# IRComms.net
KiCad netlist of a schematic drawn in Altium Designer
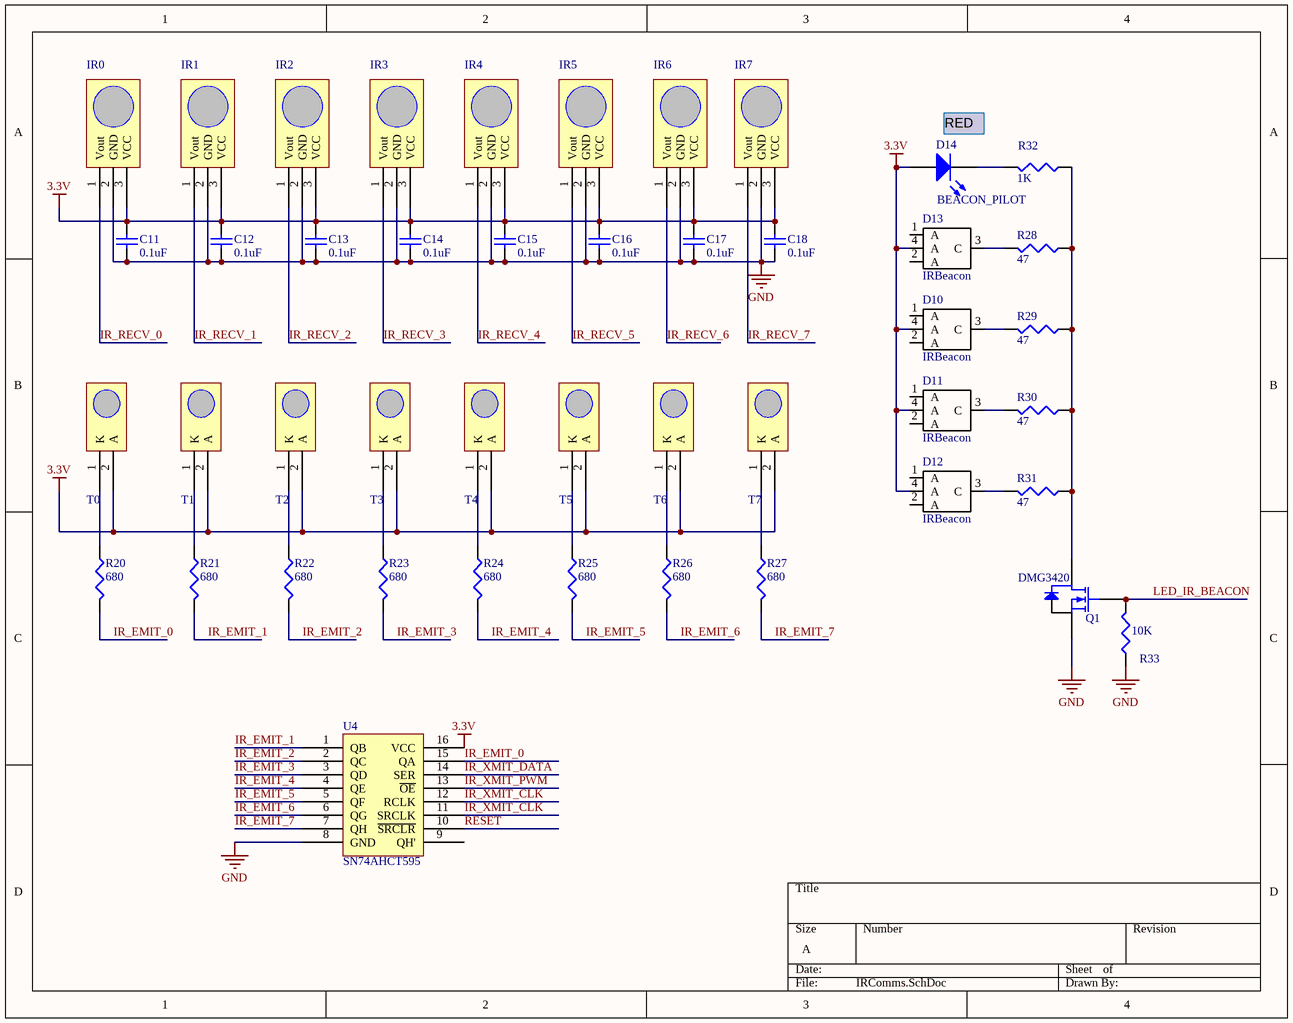
[diagram p0: IRComms.SchDoc]

(export (version "E")
  (design (tool "Eeschema 10.0.6"))
  (components
    (comp (ref "C11")
      (value "0.1uF")
      (footprint "CAPC1005L")
      (description "Capacitor (Semiconductor SIM Model)")
      (fields (field (name "Comment") "Cap Semi") (field (name "PUBLISHER") "Altium Limited"))
      (libsource (lib "Miscellaneous Devices") (part "Cap Semi"))
    )
    (comp (ref "C12")
      (value "0.1uF")
      (footprint "CAPC1005L")
      (description "Capacitor (Semiconductor SIM Model)")
      (fields (field (name "Comment") "Cap Semi") (field (name "PUBLISHER") "Altium Limited"))
      (libsource (lib "Miscellaneous Devices") (part "Cap Semi"))
    )
    (comp (ref "C13")
      (value "0.1uF")
      (footprint "CAPC1005L")
      (description "Capacitor (Semiconductor SIM Model)")
      (fields (field (name "Comment") "Cap Semi") (field (name "PUBLISHER") "Altium Limited"))
      (libsource (lib "Miscellaneous Devices") (part "Cap Semi"))
    )
    (comp (ref "C14")
      (value "0.1uF")
      (footprint "CAPC1005L")
      (description "Capacitor (Semiconductor SIM Model)")
      (fields (field (name "Comment") "Cap Semi") (field (name "PUBLISHER") "Altium Limited"))
      (libsource (lib "Miscellaneous Devices") (part "Cap Semi"))
    )
    (comp (ref "C15")
      (value "0.1uF")
      (footprint "CAPC1005L")
      (description "Capacitor (Semiconductor SIM Model)")
      (fields (field (name "Comment") "Cap Semi") (field (name "PUBLISHER") "Altium Limited"))
      (libsource (lib "Miscellaneous Devices") (part "Cap Semi"))
    )
    (comp (ref "C16")
      (value "0.1uF")
      (footprint "CAPC1005L")
      (description "Capacitor (Semiconductor SIM Model)")
      (fields (field (name "Comment") "Cap Semi") (field (name "PUBLISHER") "Altium Limited"))
      (libsource (lib "Miscellaneous Devices") (part "Cap Semi"))
    )
    (comp (ref "C17")
      (value "0.1uF")
      (footprint "CAPC1005L")
      (description "Capacitor (Semiconductor SIM Model)")
      (fields (field (name "Comment") "Cap Semi") (field (name "PUBLISHER") "Altium Limited"))
      (libsource (lib "Miscellaneous Devices") (part "Cap Semi"))
    )
    (comp (ref "C18")
      (value "0.1uF")
      (footprint "CAPC1005L")
      (description "Capacitor (Semiconductor SIM Model)")
      (fields (field (name "Comment") "Cap Semi") (field (name "PUBLISHER") "Altium Limited"))
      (libsource (lib "Miscellaneous Devices") (part "Cap Semi"))
    )
    (comp (ref "D10") (value "IRBeacon") (footprint "IRBeacon") (libsource (lib "mrone") (part "IRBeacon")))
    (comp (ref "D11") (value "IRBeacon") (footprint "IRBeacon") (libsource (lib "mrone") (part "IRBeacon")))
    (comp (ref "D12") (value "IRBeacon") (footprint "IRBeacon") (libsource (lib "mrone") (part "IRBeacon")))
    (comp (ref "D13") (value "IRBeacon") (footprint "IRBeacon") (libsource (lib "mrone") (part "IRBeacon")))
    (comp (ref "D14")
      (value "BEACON_PILOT")
      (footprint "SurfaceMount(603)")
      (libsource (lib "mrone") (part "LED"))
    )
    (comp (ref "IR0")
      (value "GP1UX31QS")
      (footprint "GP1UX31QS")
      (libsource (lib "mrone") (part "GP1UX31QS"))
    )
    (comp (ref "IR1")
      (value "GP1UX31QS")
      (footprint "GP1UX31QS")
      (libsource (lib "mrone") (part "GP1UX31QS"))
    )
    (comp (ref "IR2")
      (value "GP1UX31QS")
      (footprint "GP1UX31QS")
      (libsource (lib "mrone") (part "GP1UX31QS"))
    )
    (comp (ref "IR3")
      (value "GP1UX31QS")
      (footprint "GP1UX31QS")
      (libsource (lib "mrone") (part "GP1UX31QS"))
    )
    (comp (ref "IR4")
      (value "GP1UX31QS")
      (footprint "GP1UX31QS")
      (libsource (lib "mrone") (part "GP1UX31QS"))
    )
    (comp (ref "IR5")
      (value "GP1UX31QS")
      (footprint "GP1UX31QS")
      (libsource (lib "mrone") (part "GP1UX31QS"))
    )
    (comp (ref "IR6")
      (value "GP1UX31QS")
      (footprint "GP1UX31QS")
      (libsource (lib "mrone") (part "GP1UX31QS"))
    )
    (comp (ref "IR7")
      (value "GP1UX31QS")
      (footprint "GP1UX31QS")
      (libsource (lib "mrone") (part "GP1UX31QS"))
    )
    (comp (ref "Q1")
      (value "Mosfet")
      (footprint "SOT-23")
      (fields (field (name "MPN") "DMG3420"))
      (libsource (lib "mrone") (part "Mosfet"))
    )
    (comp (ref "R20")
      (value "680")
      (footprint "RESC1608L")
      (description "Resistor")
      (fields (field (name "Comment") "Res3") (field (name "PUBLISHER") "Altium Limited"))
      (libsource (lib "Miscellaneous Devices") (part "Res3"))
    )
    (comp (ref "R21")
      (value "680")
      (footprint "RESC1608L")
      (description "Resistor")
      (fields (field (name "Comment") "Res3") (field (name "PUBLISHER") "Altium Limited"))
      (libsource (lib "Miscellaneous Devices") (part "Res3"))
    )
    (comp (ref "R22")
      (value "680")
      (footprint "RESC1608L")
      (description "Resistor")
      (fields (field (name "Comment") "Res3") (field (name "PUBLISHER") "Altium Limited"))
      (libsource (lib "Miscellaneous Devices") (part "Res3"))
    )
    (comp (ref "R23")
      (value "680")
      (footprint "RESC1608L")
      (description "Resistor")
      (fields (field (name "Comment") "Res3") (field (name "PUBLISHER") "Altium Limited"))
      (libsource (lib "Miscellaneous Devices") (part "Res3"))
    )
    (comp (ref "R24")
      (value "680")
      (footprint "RESC1608L")
      (description "Resistor")
      (fields (field (name "Comment") "Res3") (field (name "PUBLISHER") "Altium Limited"))
      (libsource (lib "Miscellaneous Devices") (part "Res3"))
    )
    (comp (ref "R25")
      (value "680")
      (footprint "RESC1608L")
      (description "Resistor")
      (fields (field (name "Comment") "Res3") (field (name "PUBLISHER") "Altium Limited"))
      (libsource (lib "Miscellaneous Devices") (part "Res3"))
    )
    (comp (ref "R26")
      (value "680")
      (footprint "RESC1608L")
      (description "Resistor")
      (fields (field (name "Comment") "Res3") (field (name "PUBLISHER") "Altium Limited"))
      (libsource (lib "Miscellaneous Devices") (part "Res3"))
    )
    (comp (ref "R27")
      (value "680")
      (footprint "RESC1608L")
      (description "Resistor")
      (fields (field (name "Comment") "Res3") (field (name "PUBLISHER") "Altium Limited"))
      (libsource (lib "Miscellaneous Devices") (part "Res3"))
    )
    (comp (ref "R28")
      (value "47")
      (footprint "RESC1608L")
      (description "Resistor")
      (fields (field (name "Comment") "Res3") (field (name "PUBLISHER") "Altium Limited"))
      (libsource (lib "Miscellaneous Devices") (part "Res3"))
    )
    (comp (ref "R29")
      (value "47")
      (footprint "RESC1608L")
      (description "Resistor")
      (fields (field (name "Comment") "Res3") (field (name "PUBLISHER") "Altium Limited"))
      (libsource (lib "Miscellaneous Devices") (part "Res3"))
    )
    (comp (ref "R30")
      (value "47")
      (footprint "RESC1608L")
      (description "Resistor")
      (fields (field (name "Comment") "Res3") (field (name "PUBLISHER") "Altium Limited"))
      (libsource (lib "Miscellaneous Devices") (part "Res3"))
    )
    (comp (ref "R31")
      (value "47")
      (footprint "RESC1608L")
      (description "Resistor")
      (fields (field (name "Comment") "Res3") (field (name "PUBLISHER") "Altium Limited"))
      (libsource (lib "Miscellaneous Devices") (part "Res3"))
    )
    (comp (ref "R32")
      (value "1K")
      (footprint "RESC1608L")
      (description "Resistor")
      (fields (field (name "Comment") "Res3") (field (name "PUBLISHER") "Altium Limited"))
      (libsource (lib "Miscellaneous Devices") (part "Res3"))
    )
    (comp (ref "R33")
      (value "10K")
      (footprint "RESC1608L")
      (description "Resistor")
      (fields (field (name "Comment") "Res3") (field (name "PUBLISHER") "Altium Limited"))
      (libsource (lib "Miscellaneous Devices") (part "Res3"))
    )
    (comp (ref "T0") (value "LN54") (footprint "LN54") (libsource (lib "mrone") (part "LN54")))
    (comp (ref "T1") (value "LN54") (footprint "LN54") (libsource (lib "mrone") (part "LN54")))
    (comp (ref "T2") (value "LN54") (footprint "LN54") (libsource (lib "mrone") (part "LN54")))
    (comp (ref "T3") (value "LN54") (footprint "LN54") (libsource (lib "mrone") (part "LN54")))
    (comp (ref "T4") (value "LN54") (footprint "LN54") (libsource (lib "mrone") (part "LN54")))
    (comp (ref "T5") (value "LN54") (footprint "LN54") (libsource (lib "mrone") (part "LN54")))
    (comp (ref "T6") (value "LN54") (footprint "LN54") (libsource (lib "mrone") (part "LN54")))
    (comp (ref "T7") (value "LN54") (footprint "LN54") (libsource (lib "mrone") (part "LN54")))
    (comp (ref "U4")
      (value "SN74AHCT595")
      (footprint "TSSOP-16")
      (description "shift register")
      (libsource (lib "mrone") (part "SN74AHCT595"))
    )
  )
  (nets
    (net (code "1") (name "/IR_EMIT_0") (class "Default")
      (node (ref "R20") (pin "2") (pinfunction "2_2") (pintype "passive"))
      (node (ref "U4") (pin "15") (pinfunction "QA_15") (pintype "passive"))
    )
    (net (code "2") (name "/IR_EMIT_1") (class "Default")
      (node (ref "R21") (pin "2") (pinfunction "2_2") (pintype "passive"))
      (node (ref "U4") (pin "1") (pinfunction "QB_1") (pintype "passive"))
    )
    (net (code "3") (name "/IR_EMIT_2") (class "Default")
      (node (ref "R22") (pin "2") (pinfunction "2_2") (pintype "passive"))
      (node (ref "U4") (pin "2") (pinfunction "QC_2") (pintype "passive"))
    )
    (net (code "4") (name "/IR_EMIT_3") (class "Default")
      (node (ref "R23") (pin "2") (pinfunction "2_2") (pintype "passive"))
      (node (ref "U4") (pin "3") (pinfunction "QD_3") (pintype "passive"))
    )
    (net (code "5") (name "/IR_EMIT_4") (class "Default")
      (node (ref "R24") (pin "2") (pinfunction "2_2") (pintype "passive"))
      (node (ref "U4") (pin "4") (pinfunction "QE_4") (pintype "passive"))
    )
    (net (code "6") (name "/IR_EMIT_5") (class "Default")
      (node (ref "R25") (pin "2") (pinfunction "2_2") (pintype "passive"))
      (node (ref "U4") (pin "5") (pinfunction "QF_5") (pintype "passive"))
    )
    (net (code "7") (name "/IR_EMIT_6") (class "Default")
      (node (ref "R26") (pin "2") (pinfunction "2_2") (pintype "passive"))
      (node (ref "U4") (pin "6") (pinfunction "QG_6") (pintype "passive"))
    )
    (net (code "8") (name "/IR_EMIT_7") (class "Default")
      (node (ref "R27") (pin "2") (pinfunction "2_2") (pintype "passive"))
      (node (ref "U4") (pin "7") (pinfunction "QH_7") (pintype "passive"))
    )
    (net (code "9") (name "/IR_RECV_0") (class "Default")
      (node (ref "IR0") (pin "1") (pinfunction "Vout_1") (pintype "passive"))
    )
    (net (code "10") (name "/IR_RECV_1") (class "Default")
      (node (ref "IR1") (pin "1") (pinfunction "Vout_1") (pintype "passive"))
    )
    (net (code "11") (name "/IR_RECV_2") (class "Default")
      (node (ref "IR2") (pin "1") (pinfunction "Vout_1") (pintype "passive"))
    )
    (net (code "12") (name "/IR_RECV_3") (class "Default")
      (node (ref "IR3") (pin "1") (pinfunction "Vout_1") (pintype "passive"))
    )
    (net (code "13") (name "/IR_RECV_4") (class "Default")
      (node (ref "IR4") (pin "1") (pinfunction "Vout_1") (pintype "passive"))
    )
    (net (code "14") (name "/IR_RECV_5") (class "Default")
      (node (ref "IR5") (pin "1") (pinfunction "Vout_1") (pintype "passive"))
    )
    (net (code "15") (name "/IR_RECV_6") (class "Default")
      (node (ref "IR6") (pin "1") (pinfunction "Vout_1") (pintype "passive"))
    )
    (net (code "16") (name "/IR_RECV_7") (class "Default")
      (node (ref "IR7") (pin "1") (pinfunction "Vout_1") (pintype "passive"))
    )
    (net (code "17") (name "/IR_XMIT_CLK") (class "Default")
      (node (ref "U4") (pin "11") (pinfunction "SRCLK_11") (pintype "passive"))
      (node (ref "U4") (pin "12") (pinfunction "RCLK_12") (pintype "passive"))
    )
    (net (code "18") (name "/IR_XMIT_DATA") (class "Default")
      (node (ref "U4") (pin "14") (pinfunction "SER_14") (pintype "passive"))
    )
    (net (code "19") (name "/IR_XMIT_PWM") (class "Default")
      (node (ref "U4") (pin "13") (pinfunction "~{OE}_13") (pintype "passive"))
    )
    (net (code "20") (name "/LED_IR_BEACON") (class "Default")
      (node (ref "Q1") (pin "1") (pinfunction "G_1") (pintype "passive"))
      (node (ref "R33") (pin "2") (pinfunction "2_2") (pintype "passive"))
    )
    (net (code "21") (name "/RESET") (class "Default")
      (node (ref "U4") (pin "10") (pinfunction "~{SRCLR}_10") (pintype "passive"))
    )
    (net (code "22") (name "3.3V") (class "Default")
      (node (ref "C11") (pin "2") (pinfunction "2_2") (pintype "passive"))
      (node (ref "C12") (pin "2") (pinfunction "2_2") (pintype "passive"))
      (node (ref "C13") (pin "2") (pinfunction "2_2") (pintype "passive"))
      (node (ref "C14") (pin "2") (pinfunction "2_2") (pintype "passive"))
      (node (ref "C15") (pin "2") (pinfunction "2_2") (pintype "passive"))
      (node (ref "C16") (pin "2") (pinfunction "2_2") (pintype "passive"))
      (node (ref "C17") (pin "2") (pinfunction "2_2") (pintype "passive"))
      (node (ref "C18") (pin "2") (pinfunction "2_2") (pintype "passive"))
      (node (ref "D10") (pin "4") (pinfunction "A_4") (pintype "passive"))
      (node (ref "D11") (pin "4") (pinfunction "A_4") (pintype "passive"))
      (node (ref "D12") (pin "4") (pinfunction "A_4") (pintype "passive"))
      (node (ref "D13") (pin "4") (pinfunction "A_4") (pintype "passive"))
      (node (ref "D14") (pin "1") (pinfunction "A_1") (pintype "passive"))
      (node (ref "IR0") (pin "3") (pinfunction "VCC_3") (pintype "power_in"))
      (node (ref "IR1") (pin "3") (pinfunction "VCC_3") (pintype "power_in"))
      (node (ref "IR2") (pin "3") (pinfunction "VCC_3") (pintype "power_in"))
      (node (ref "IR3") (pin "3") (pinfunction "VCC_3") (pintype "power_in"))
      (node (ref "IR4") (pin "3") (pinfunction "VCC_3") (pintype "power_in"))
      (node (ref "IR5") (pin "3") (pinfunction "VCC_3") (pintype "power_in"))
      (node (ref "IR6") (pin "3") (pinfunction "VCC_3") (pintype "power_in"))
      (node (ref "IR7") (pin "3") (pinfunction "VCC_3") (pintype "power_in"))
      (node (ref "T0") (pin "2") (pinfunction "A_2") (pintype "passive"))
      (node (ref "T1") (pin "2") (pinfunction "A_2") (pintype "passive"))
      (node (ref "T2") (pin "2") (pinfunction "A_2") (pintype "passive"))
      (node (ref "T3") (pin "2") (pinfunction "A_2") (pintype "passive"))
      (node (ref "T4") (pin "2") (pinfunction "A_2") (pintype "passive"))
      (node (ref "T5") (pin "2") (pinfunction "A_2") (pintype "passive"))
      (node (ref "T6") (pin "2") (pinfunction "A_2") (pintype "passive"))
      (node (ref "T7") (pin "2") (pinfunction "A_2") (pintype "passive"))
      (node (ref "U4") (pin "16") (pinfunction "VCC_16") (pintype "passive"))
    )
    (net (code "23") (name "GND") (class "Default")
      (node (ref "C11") (pin "1") (pinfunction "1_1") (pintype "passive"))
      (node (ref "C12") (pin "1") (pinfunction "1_1") (pintype "passive"))
      (node (ref "C13") (pin "1") (pinfunction "1_1") (pintype "passive"))
      (node (ref "C14") (pin "1") (pinfunction "1_1") (pintype "passive"))
      (node (ref "C15") (pin "1") (pinfunction "1_1") (pintype "passive"))
      (node (ref "C16") (pin "1") (pinfunction "1_1") (pintype "passive"))
      (node (ref "C17") (pin "1") (pinfunction "1_1") (pintype "passive"))
      (node (ref "C18") (pin "1") (pinfunction "1_1") (pintype "passive"))
      (node (ref "IR0") (pin "2") (pinfunction "GND_2") (pintype "power_in"))
      (node (ref "IR1") (pin "2") (pinfunction "GND_2") (pintype "power_in"))
      (node (ref "IR2") (pin "2") (pinfunction "GND_2") (pintype "power_in"))
      (node (ref "IR3") (pin "2") (pinfunction "GND_2") (pintype "power_in"))
      (node (ref "IR4") (pin "2") (pinfunction "GND_2") (pintype "power_in"))
      (node (ref "IR5") (pin "2") (pinfunction "GND_2") (pintype "power_in"))
      (node (ref "IR6") (pin "2") (pinfunction "GND_2") (pintype "power_in"))
      (node (ref "IR7") (pin "2") (pinfunction "GND_2") (pintype "power_in"))
      (node (ref "Q1") (pin "2") (pinfunction "S_2") (pintype "passive"))
      (node (ref "R33") (pin "1") (pinfunction "1_1") (pintype "passive"))
      (node (ref "U4") (pin "8") (pinfunction "GND_8") (pintype "passive"))
    )
    (net (code "24") (name "Net-(D10-C)") (class "Default")
      (node (ref "D10") (pin "3") (pinfunction "C_3") (pintype "passive"))
      (node (ref "R29") (pin "2") (pinfunction "2_2") (pintype "passive"))
    )
    (net (code "25") (name "Net-(D11-C)") (class "Default")
      (node (ref "D11") (pin "3") (pinfunction "C_3") (pintype "passive"))
      (node (ref "R30") (pin "2") (pinfunction "2_2") (pintype "passive"))
    )
    (net (code "26") (name "Net-(D12-C)") (class "Default")
      (node (ref "D12") (pin "3") (pinfunction "C_3") (pintype "passive"))
      (node (ref "R31") (pin "2") (pinfunction "2_2") (pintype "passive"))
    )
    (net (code "27") (name "Net-(D13-C)") (class "Default")
      (node (ref "D13") (pin "3") (pinfunction "C_3") (pintype "passive"))
      (node (ref "R28") (pin "2") (pinfunction "2_2") (pintype "passive"))
    )
    (net (code "28") (name "Net-(D14-K)") (class "Default")
      (node (ref "D14") (pin "2") (pinfunction "K_2") (pintype "passive"))
      (node (ref "R32") (pin "2") (pinfunction "2_2") (pintype "passive"))
    )
    (net (code "29") (name "Net-(Q1-D)") (class "Default")
      (node (ref "Q1") (pin "3") (pinfunction "D_3") (pintype "passive"))
      (node (ref "R28") (pin "1") (pinfunction "1_1") (pintype "passive"))
      (node (ref "R29") (pin "1") (pinfunction "1_1") (pintype "passive"))
      (node (ref "R30") (pin "1") (pinfunction "1_1") (pintype "passive"))
      (node (ref "R31") (pin "1") (pinfunction "1_1") (pintype "passive"))
      (node (ref "R32") (pin "1") (pinfunction "1_1") (pintype "passive"))
    )
    (net (code "30") (name "Net-(T0-K)") (class "Default")
      (node (ref "R20") (pin "1") (pinfunction "1_1") (pintype "passive"))
      (node (ref "T0") (pin "1") (pinfunction "K_1") (pintype "passive"))
    )
    (net (code "31") (name "Net-(T1-K)") (class "Default")
      (node (ref "R21") (pin "1") (pinfunction "1_1") (pintype "passive"))
      (node (ref "T1") (pin "1") (pinfunction "K_1") (pintype "passive"))
    )
    (net (code "32") (name "Net-(T2-K)") (class "Default")
      (node (ref "R22") (pin "1") (pinfunction "1_1") (pintype "passive"))
      (node (ref "T2") (pin "1") (pinfunction "K_1") (pintype "passive"))
    )
    (net (code "33") (name "Net-(T3-K)") (class "Default")
      (node (ref "R23") (pin "1") (pinfunction "1_1") (pintype "passive"))
      (node (ref "T3") (pin "1") (pinfunction "K_1") (pintype "passive"))
    )
    (net (code "34") (name "Net-(T4-K)") (class "Default")
      (node (ref "R24") (pin "1") (pinfunction "1_1") (pintype "passive"))
      (node (ref "T4") (pin "1") (pinfunction "K_1") (pintype "passive"))
    )
    (net (code "35") (name "Net-(T5-K)") (class "Default")
      (node (ref "R25") (pin "1") (pinfunction "1_1") (pintype "passive"))
      (node (ref "T5") (pin "1") (pinfunction "K_1") (pintype "passive"))
    )
    (net (code "36") (name "Net-(T6-K)") (class "Default")
      (node (ref "R26") (pin "1") (pinfunction "1_1") (pintype "passive"))
      (node (ref "T6") (pin "1") (pinfunction "K_1") (pintype "passive"))
    )
    (net (code "37") (name "Net-(T7-K)") (class "Default")
      (node (ref "R27") (pin "1") (pinfunction "1_1") (pintype "passive"))
      (node (ref "T7") (pin "1") (pinfunction "K_1") (pintype "passive"))
    )
    (net (code "38") (name "unconnected-(D10-A-Pad1)") (class "Default")
      (node (ref "D10") (pin "1") (pinfunction "A_1") (pintype "passive"))
    )
    (net (code "39") (name "unconnected-(D10-A-Pad2)") (class "Default")
      (node (ref "D10") (pin "2") (pinfunction "A_2") (pintype "passive"))
    )
    (net (code "40") (name "unconnected-(D11-A-Pad1)") (class "Default")
      (node (ref "D11") (pin "1") (pinfunction "A_1") (pintype "passive"))
    )
    (net (code "41") (name "unconnected-(D11-A-Pad2)") (class "Default")
      (node (ref "D11") (pin "2") (pinfunction "A_2") (pintype "passive"))
    )
    (net (code "42") (name "unconnected-(D12-A-Pad1)") (class "Default")
      (node (ref "D12") (pin "1") (pinfunction "A_1") (pintype "passive"))
    )
    (net (code "43") (name "unconnected-(D12-A-Pad2)") (class "Default")
      (node (ref "D12") (pin "2") (pinfunction "A_2") (pintype "passive"))
    )
    (net (code "44") (name "unconnected-(D13-A-Pad1)") (class "Default")
      (node (ref "D13") (pin "1") (pinfunction "A_1") (pintype "passive"))
    )
    (net (code "45") (name "unconnected-(D13-A-Pad2)") (class "Default")
      (node (ref "D13") (pin "2") (pinfunction "A_2") (pintype "passive"))
    )
    (net (code "46") (name "unconnected-(U4-QH'-Pad9)") (class "Default")
      (node (ref "U4") (pin "9") (pinfunction "QH'_9") (pintype "passive"))
    )
  )
)
